# VFD_alpha_Sheet1.net
KiCad netlist of a schematic drawn in Altium Designer
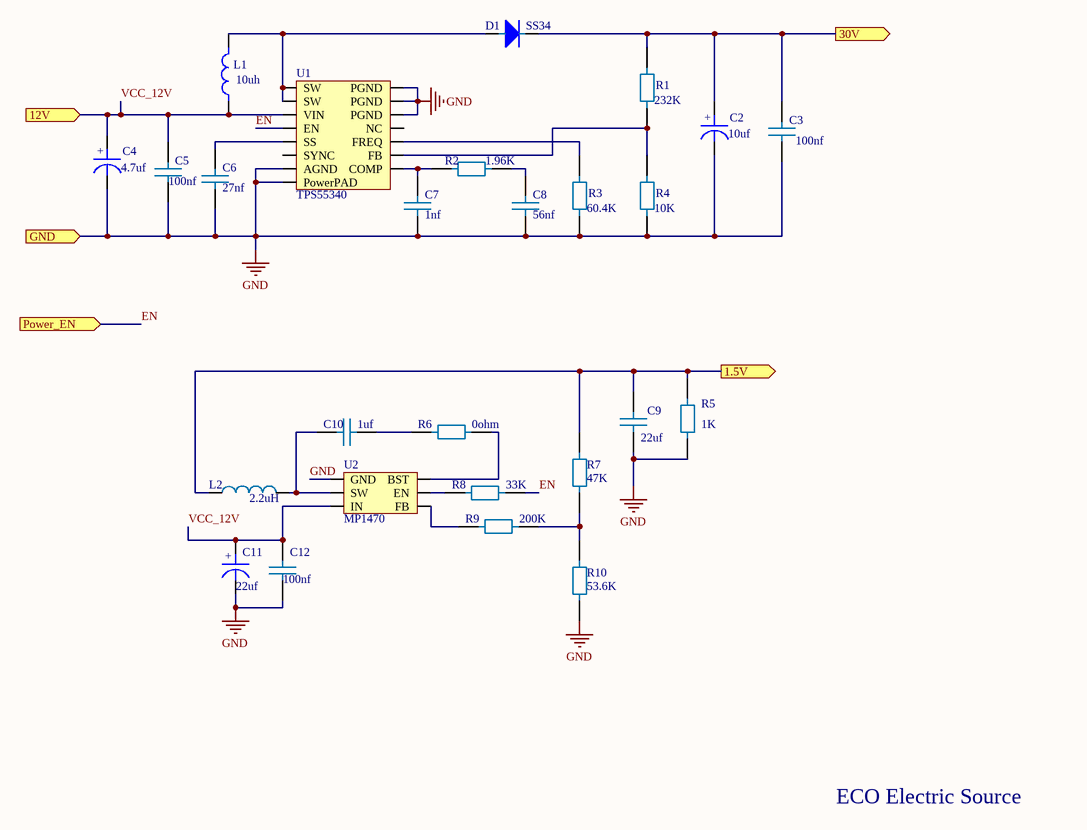
[diagram p0: VFD_alpha_Sheet1.SchDoc]

(export (version "E")
  (design (tool "Eeschema 10.0.6"))
  (components
    (comp (ref "C2") (value "10uf") (footprint "CAP_5_2") (libsource (lib "ZZB_Lib") (part "CAP_D5")))
    (comp (ref "C3")
      (value "100nf")
      (footprint "0805")
      (fields (field (name "Comment") "C(0805)"))
      (libsource (lib "ZZB_Lib") (part "C(0805)"))
    )
    (comp (ref "C4") (value "4.7uf") (footprint "CAP_5_2") (libsource (lib "ZZB_Lib") (part "CAP_D5")))
    (comp (ref "C5")
      (value "100nf")
      (footprint "0805")
      (fields (field (name "Comment") "C(0805)"))
      (libsource (lib "ZZB_Lib") (part "C(0805)"))
    )
    (comp (ref "C6")
      (value "27nf")
      (footprint "0805")
      (fields (field (name "Comment") "C(0805)"))
      (libsource (lib "ZZB_Lib") (part "C(0805)"))
    )
    (comp (ref "C7")
      (value "1nf")
      (footprint "0805")
      (fields (field (name "Comment") "C(0805)"))
      (libsource (lib "ZZB_Lib") (part "C(0805)"))
    )
    (comp (ref "C8")
      (value "56nf")
      (footprint "0805")
      (fields (field (name "Comment") "C(0805)"))
      (libsource (lib "ZZB_Lib") (part "C(0805)"))
    )
    (comp (ref "C9")
      (value "22uf")
      (footprint "1206")
      (fields (field (name "Comment") "C(1206)"))
      (libsource (lib "ZZB_Lib") (part "C(1206)"))
    )
    (comp (ref "C10")
      (value "1uf")
      (footprint "0805")
      (fields (field (name "Comment") "C(0805)"))
      (libsource (lib "ZZB_Lib") (part "C(0805)"))
    )
    (comp (ref "C11")
      (value "22uf")
      (footprint "CAP_5_2")
      (fields (field (name "Comment") "CAP_D5"))
      (libsource (lib "ZZB_Lib") (part "CAP_D5"))
    )
    (comp (ref "C12")
      (value "100nf")
      (footprint "0805")
      (fields (field (name "Comment") "C(0805)"))
      (libsource (lib "ZZB_Lib") (part "C(0805)"))
    )
    (comp (ref "D1") (value "SS34") (footprint "DO-214AC") (libsource (lib "ZZB_Lib") (part "SS34")))
    (comp (ref "L1")
      (value "10uh")
      (footprint "INDP6.0*6.0*4.7")
      (fields (field (name "Comment") "功率电感(6045)"))
      (libsource (lib "ZZB_Lib") (part "功率电感(6045)"))
    )
    (comp (ref "L2")
      (value "2.2uH")
      (footprint "INDP3.0*3.0*1.5")
      (fields (field (name "Comment") "功率电感(3015)"))
      (libsource (lib "ZZB_Lib") (part "功率电感(3015)"))
    )
    (comp (ref "R1")
      (value "232K")
      (footprint "0805")
      (fields (field (name "Comment") "R(0805)"))
      (libsource (lib "ZZB_Lib") (part "R(0805)"))
    )
    (comp (ref "R2")
      (value "1.96K")
      (footprint "0805")
      (fields (field (name "Comment") "R(0805)"))
      (libsource (lib "ZZB_Lib") (part "R(0805)"))
    )
    (comp (ref "R3")
      (value "60.4K")
      (footprint "0805")
      (fields (field (name "Comment") "R(0805)"))
      (libsource (lib "ZZB_Lib") (part "R(0805)"))
    )
    (comp (ref "R4")
      (value "10K")
      (footprint "0805")
      (fields (field (name "Comment") "R(0805)"))
      (libsource (lib "ZZB_Lib") (part "R(0805)"))
    )
    (comp (ref "R5")
      (value "1K")
      (footprint "0805")
      (fields (field (name "Comment") "R(0805)"))
      (libsource (lib "ZZB_Lib") (part "R(0805)"))
    )
    (comp (ref "R6")
      (value "0ohm")
      (footprint "0805")
      (fields (field (name "Comment") "R(0805)"))
      (libsource (lib "ZZB_Lib") (part "R(0805)"))
    )
    (comp (ref "R7")
      (value "47K")
      (footprint "0805")
      (fields (field (name "Comment") "R(0805)"))
      (libsource (lib "ZZB_Lib") (part "R(0805)"))
    )
    (comp (ref "R8")
      (value "33K")
      (footprint "0805")
      (fields (field (name "Comment") "R(0805)"))
      (libsource (lib "ZZB_Lib") (part "R(0805)"))
    )
    (comp (ref "R9")
      (value "200K")
      (footprint "0805")
      (fields (field (name "Comment") "R(0805)"))
      (libsource (lib "ZZB_Lib") (part "R(0805)"))
    )
    (comp (ref "R10")
      (value "53.6K")
      (footprint "0805")
      (fields (field (name "Comment") "R(0805)"))
      (libsource (lib "ZZB_Lib") (part "R(0805)"))
    )
    (comp (ref "U1")
      (value "TPS55340")
      (footprint "PWP_TPS55340")
      (libsource (lib "ZZB_Lib") (part "TPS55340"))
    )
    (comp (ref "U2")
      (value "MP1470")
      (footprint "SOT95-6N-MT3608")
      (libsource (lib "ZZB_Lib") (part "MP1470"))
    )
  )
  (nets
    (net (code "1") (name "/1.5V") (class "Default")
      (node (ref "C9") (pin "2") (pinfunction "2_2") (pintype "passive"))
      (node (ref "L2") (pin "1") (pintype "passive"))
      (node (ref "R5") (pin "2") (pinfunction "2_2") (pintype "passive"))
      (node (ref "R7") (pin "2") (pinfunction "2_2") (pintype "passive"))
    )
    (net (code "2") (name "/30V") (class "Default")
      (node (ref "C2") (pin "1") (pinfunction "1_1") (pintype "passive"))
      (node (ref "C3") (pin "2") (pinfunction "2_2") (pintype "passive"))
      (node (ref "D1") (pin "2") (pinfunction "2_2") (pintype "passive"))
      (node (ref "R1") (pin "2") (pinfunction "2_2") (pintype "passive"))
    )
    (net (code "3") (name "/EN") (class "Default")
      (node (ref "R8") (pin "2") (pinfunction "2_2") (pintype "passive"))
      (node (ref "U1") (pin "4") (pinfunction "EN_4") (pintype "passive"))
    )
    (net (code "4") (name "/VCC_12V") (class "Default")
      (node (ref "C11") (pin "1") (pinfunction "1_1") (pintype "passive"))
      (node (ref "C12") (pin "2") (pinfunction "2_2") (pintype "passive"))
      (node (ref "C4") (pin "1") (pinfunction "1_1") (pintype "passive"))
      (node (ref "C5") (pin "2") (pinfunction "2_2") (pintype "passive"))
      (node (ref "L1") (pin "1") (pinfunction "1_1") (pintype "passive"))
      (node (ref "U1") (pin "3") (pinfunction "VIN_3") (pintype "passive"))
      (node (ref "U2") (pin "3") (pinfunction "IN_3") (pintype "passive"))
    )
    (net (code "5") (name "GND") (class "Default")
      (node (ref "C11") (pin "2") (pinfunction "2_2") (pintype "passive"))
      (node (ref "C12") (pin "1") (pinfunction "1_1") (pintype "passive"))
      (node (ref "C2") (pin "2") (pinfunction "2_2") (pintype "passive"))
      (node (ref "C3") (pin "1") (pinfunction "1_1") (pintype "passive"))
      (node (ref "C4") (pin "2") (pinfunction "2_2") (pintype "passive"))
      (node (ref "C5") (pin "1") (pinfunction "1_1") (pintype "passive"))
      (node (ref "C6") (pin "1") (pinfunction "1_1") (pintype "passive"))
      (node (ref "C7") (pin "1") (pinfunction "1_1") (pintype "passive"))
      (node (ref "C8") (pin "2") (pinfunction "2_2") (pintype "passive"))
      (node (ref "C9") (pin "1") (pinfunction "1_1") (pintype "passive"))
      (node (ref "R10") (pin "1") (pinfunction "1_1") (pintype "passive"))
      (node (ref "R3") (pin "1") (pinfunction "1_1") (pintype "passive"))
      (node (ref "R4") (pin "1") (pinfunction "1_1") (pintype "passive"))
      (node (ref "R5") (pin "1") (pinfunction "1_1") (pintype "passive"))
      (node (ref "U1") (pin "0") (pinfunction "PowerPAD_0") (pintype "passive"))
      (node (ref "U1") (pin "12") (pinfunction "PGND_12") (pintype "passive"))
      (node (ref "U1") (pin "13") (pinfunction "PGND_13") (pintype "passive"))
      (node (ref "U1") (pin "14") (pinfunction "PGND_14") (pintype "passive"))
      (node (ref "U1") (pin "7") (pinfunction "AGND_7") (pintype "passive"))
      (node (ref "U2") (pin "1") (pinfunction "GND_1") (pintype "passive"))
    )
    (net (code "6") (name "Net-(C8-Pad1)") (class "Default")
      (node (ref "C8") (pin "1") (pinfunction "1_1") (pintype "passive"))
      (node (ref "R2") (pin "2") (pinfunction "2_2") (pintype "passive"))
    )
    (net (code "7") (name "Net-(C10-Pad2)") (class "Default")
      (node (ref "C10") (pin "2") (pinfunction "2_2") (pintype "passive"))
      (node (ref "R6") (pin "1") (pinfunction "1_1") (pintype "passive"))
    )
    (net (code "8") (name "Net-(D1-Pad1)") (class "Default")
      (node (ref "D1") (pin "1") (pinfunction "1_1") (pintype "passive"))
      (node (ref "L1") (pin "2") (pinfunction "2_2") (pintype "passive"))
      (node (ref "U1") (pin "1") (pinfunction "SW_1") (pintype "passive"))
      (node (ref "U1") (pin "2") (pinfunction "SW_2") (pintype "passive"))
    )
    (net (code "9") (name "Net-(R10-Pad2)") (class "Default")
      (node (ref "R10") (pin "2") (pinfunction "2_2") (pintype "passive"))
      (node (ref "R7") (pin "1") (pinfunction "1_1") (pintype "passive"))
      (node (ref "R9") (pin "2") (pinfunction "2_2") (pintype "passive"))
    )
    (net (code "10") (name "Net-(U1-COMP)") (class "Default")
      (node (ref "C7") (pin "2") (pinfunction "2_2") (pintype "passive"))
      (node (ref "R2") (pin "1") (pinfunction "1_1") (pintype "passive"))
      (node (ref "U1") (pin "8") (pinfunction "COMP_8") (pintype "passive"))
    )
    (net (code "11") (name "Net-(U1-FB)") (class "Default")
      (node (ref "R1") (pin "1") (pinfunction "1_1") (pintype "passive"))
      (node (ref "R4") (pin "2") (pinfunction "2_2") (pintype "passive"))
      (node (ref "U1") (pin "9") (pinfunction "FB_9") (pintype "passive"))
    )
    (net (code "12") (name "Net-(U1-FREQ)") (class "Default")
      (node (ref "R3") (pin "2") (pinfunction "2_2") (pintype "passive"))
      (node (ref "U1") (pin "10") (pinfunction "FREQ_10") (pintype "passive"))
    )
    (net (code "13") (name "Net-(U1-SS)") (class "Default")
      (node (ref "C6") (pin "2") (pinfunction "2_2") (pintype "passive"))
      (node (ref "U1") (pin "5") (pinfunction "SS_5") (pintype "passive"))
    )
    (net (code "14") (name "Net-(U2-BST)") (class "Default")
      (node (ref "R6") (pin "2") (pinfunction "2_2") (pintype "passive"))
      (node (ref "U2") (pin "6") (pinfunction "BST_6") (pintype "passive"))
    )
    (net (code "15") (name "Net-(U2-EN)") (class "Default")
      (node (ref "R8") (pin "1") (pinfunction "1_1") (pintype "passive"))
      (node (ref "U2") (pin "5") (pinfunction "EN_5") (pintype "passive"))
    )
    (net (code "16") (name "Net-(U2-FB)") (class "Default")
      (node (ref "R9") (pin "1") (pinfunction "1_1") (pintype "passive"))
      (node (ref "U2") (pin "4") (pinfunction "FB_4") (pintype "passive"))
    )
    (net (code "17") (name "Net-(U2-SW)") (class "Default")
      (node (ref "C10") (pin "1") (pinfunction "1_1") (pintype "passive"))
      (node (ref "L2") (pin "2") (pintype "passive"))
      (node (ref "U2") (pin "2") (pinfunction "SW_2") (pintype "passive"))
    )
    (net (code "18") (name "unconnected-(U1-NC-Pad11)") (class "Default")
      (node (ref "U1") (pin "11") (pinfunction "NC_11") (pintype "passive"))
    )
    (net (code "19") (name "unconnected-(U1-SYNC-Pad6)") (class "Default")
      (node (ref "U1") (pin "6") (pinfunction "SYNC_6") (pintype "passive"))
    )
  )
)
